# Adafruit_Metro_M4_Express.net
KiCad netlist of a schematic drawn in EAGLE
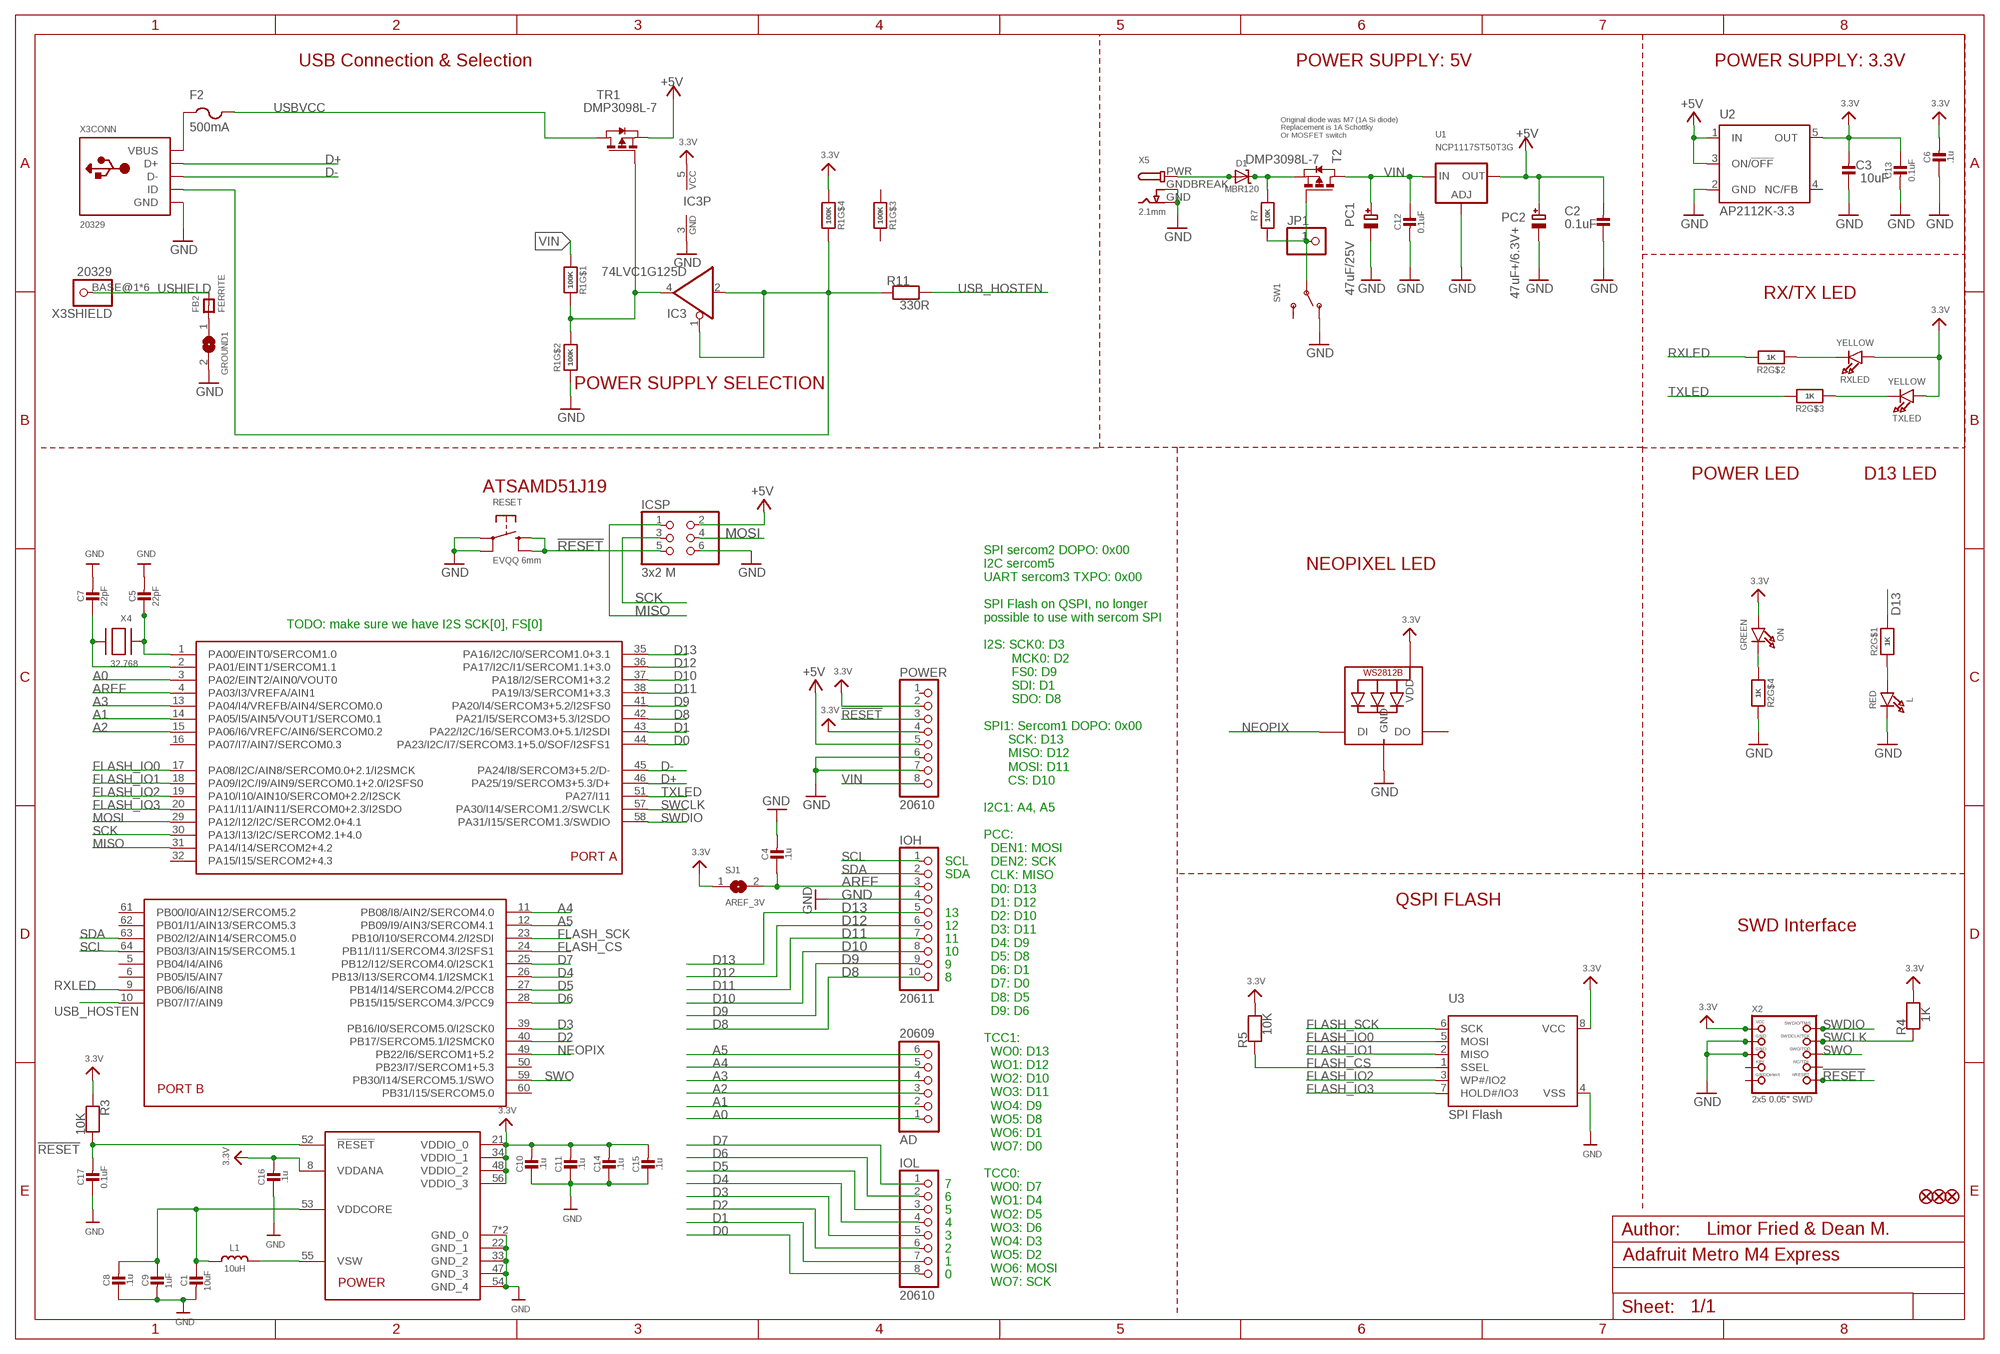
[diagram p0: schematic, sheet 1]

(export (version "E")
  (design (tool "Eeschema 10.0.6"))
  (components
    (comp (ref "AD")
      (value "20609")
      (footprint "eagle-import:1X06_OVALWAVE")
      (libsource (lib "eagle-import") (part "HEADER-1X6OVALWAVE"))
    )
    (comp (ref "C1")
      (value "10uF")
      (footprint "eagle-import:0805-NO")
      (libsource (lib "eagle-import") (part "CAP_CERAMIC0805-NOOUTLINE"))
    )
    (comp (ref "C2")
      (value "0.1uF")
      (footprint "eagle-import:0805-NO")
      (libsource (lib "eagle-import") (part "CAP_CERAMIC0805-NOOUTLINE"))
    )
    (comp (ref "C3")
      (value "10uF")
      (footprint "eagle-import:0805-NO")
      (libsource (lib "eagle-import") (part "CAP_CERAMIC0805-NOOUTLINE"))
    )
    (comp (ref "C4")
      (value ".1u")
      (footprint "eagle-import:0603-NO")
      (libsource (lib "eagle-import") (part "CAP_CERAMIC0603_NO"))
    )
    (comp (ref "C5")
      (value "22pF")
      (footprint "eagle-import:0603-NO")
      (libsource (lib "eagle-import") (part "CAP_CERAMIC0603_NO"))
    )
    (comp (ref "C6")
      (value ".1u")
      (footprint "eagle-import:0603-NO")
      (libsource (lib "eagle-import") (part "CAP_CERAMIC0603_NO"))
    )
    (comp (ref "C7")
      (value "22pF")
      (footprint "eagle-import:0603-NO")
      (libsource (lib "eagle-import") (part "CAP_CERAMIC0603_NO"))
    )
    (comp (ref "C8")
      (value ".1u")
      (footprint "eagle-import:0603-NO")
      (libsource (lib "eagle-import") (part "CAP_CERAMIC0603_NO"))
    )
    (comp (ref "C9")
      (value "1uF")
      (footprint "eagle-import:0603-NO")
      (libsource (lib "eagle-import") (part "CAP_CERAMIC0603_NO"))
    )
    (comp (ref "C10")
      (value ".1u")
      (footprint "eagle-import:0603-NO")
      (libsource (lib "eagle-import") (part "CAP_CERAMIC0603_NO"))
    )
    (comp (ref "C11")
      (value ".1u")
      (footprint "eagle-import:0603-NO")
      (libsource (lib "eagle-import") (part "CAP_CERAMIC0603_NO"))
    )
    (comp (ref "C12")
      (value "0.1uF")
      (footprint "eagle-import:0603-NO")
      (libsource (lib "eagle-import") (part "CAP_CERAMIC0603_NO"))
    )
    (comp (ref "C13")
      (value "0.1uF")
      (footprint "eagle-import:0603-NO")
      (libsource (lib "eagle-import") (part "CAP_CERAMIC0603_NO"))
    )
    (comp (ref "C14")
      (value ".1u")
      (footprint "eagle-import:0603-NO")
      (libsource (lib "eagle-import") (part "CAP_CERAMIC0603_NO"))
    )
    (comp (ref "C15")
      (value ".1u")
      (footprint "eagle-import:0603-NO")
      (libsource (lib "eagle-import") (part "CAP_CERAMIC0603_NO"))
    )
    (comp (ref "C16")
      (value ".1u")
      (footprint "eagle-import:0603-NO")
      (libsource (lib "eagle-import") (part "CAP_CERAMIC0603_NO"))
    )
    (comp (ref "C17")
      (value "0.1uF")
      (footprint "eagle-import:0603-NO")
      (libsource (lib "eagle-import") (part "CAP_CERAMIC0603_NO"))
    )
    (comp (ref "D1")
      (value "MBR120")
      (footprint "eagle-import:SOD-123")
      (libsource (lib "eagle-import") (part "DIODE-SCHOTTKYSOD-123"))
    )
    (comp (ref "F2")
      (value "500mA")
      (footprint "eagle-import:R1206")
      (libsource (lib "eagle-import") (part "PTCFUSE-1206"))
    )
    (comp (ref "FB2")
      (value "FERRITE")
      (footprint "eagle-import:0805-NO")
      (libsource (lib "eagle-import") (part "FERRITE-0805NO"))
    )
    (comp (ref "FD1")
      (value "FIDUCIAL_1MM")
      (footprint "eagle-import:FIDUCIAL_1MM")
      (libsource (lib "eagle-import") (part "FIDUCIAL_1MM"))
    )
    (comp (ref "FD2")
      (value "FIDUCIAL_1MM")
      (footprint "eagle-import:FIDUCIAL_1MM")
      (libsource (lib "eagle-import") (part "FIDUCIAL_1MM"))
    )
    (comp (ref "FD3")
      (value "FIDUCIAL_1MM")
      (footprint "eagle-import:FIDUCIAL_1MM")
      (libsource (lib "eagle-import") (part "FIDUCIAL_1MM"))
    )
    (comp (ref "GROUND1")
      (value "SOLDERJUMPERCLOSED")
      (footprint "eagle-import:SOLDERJUMPER_CLOSEDWIRE")
      (libsource (lib "eagle-import") (part "SOLDERJUMPERCLOSED"))
    )
    (comp (ref "IC3")
      (value "74LVC1G125D")
      (footprint "eagle-import:SOT23-5")
      (libsource (lib "eagle-import") (part "741G125DBVAHC"))
    )
    (comp (ref "ICSP")
      (value "3x2 M")
      (footprint "eagle-import:2X03_ROUND_70MIL")
      (libsource (lib "eagle-import") (part "HEADER-2X3"))
    )
    (comp (ref "IOH")
      (value "20611")
      (footprint "eagle-import:1X10_OVALWAVE")
      (libsource (lib "eagle-import") (part "HEADER-1X10OVALWAVE"))
    )
    (comp (ref "IOL")
      (value "20610")
      (footprint "eagle-import:1X08_OVALWAVE")
      (libsource (lib "eagle-import") (part "HEADER-1X8OVALWAVE"))
    )
    (comp (ref "JP1")
      (value "HEADER-1X1ROUND")
      (footprint "eagle-import:1X01_ROUND")
      (libsource (lib "eagle-import") (part "HEADER-1X1ROUND"))
    )
    (comp (ref "L")
      (value "RED")
      (footprint "eagle-import:CHIPLED_0805_NOOUTLINE")
      (libsource (lib "eagle-import") (part "LED0805_NOOUTLINE"))
    )
    (comp (ref "L1")
      (value "10uH")
      (footprint "eagle-import:INDUCTOR_1007")
      (libsource (lib "eagle-import") (part "INDUCTOR"))
    )
    (comp (ref "LED1")
      (value "WS2812B3535")
      (footprint "eagle-import:LED3535")
      (libsource (lib "eagle-import") (part "WS2812B3535"))
    )
    (comp (ref "ON")
      (value "GREEN")
      (footprint "eagle-import:CHIPLED_0805_NOOUTLINE")
      (libsource (lib "eagle-import") (part "LED0805_NOOUTLINE"))
    )
    (comp (ref "PC1")
      (value "47uF/25V")
      (footprint "eagle-import:PANASONIC_D")
      (libsource (lib "eagle-import") (part "CAP_ELECTROLYTICPANASONIC_D"))
    )
    (comp (ref "PC2")
      (value "47uF+/6.3V+")
      (footprint "eagle-import:PANASONIC_D")
      (libsource (lib "eagle-import") (part "CAP_ELECTROLYTICPANASONIC_D"))
    )
    (comp (ref "POWER")
      (value "20610")
      (footprint "eagle-import:1X08_OVALWAVE")
      (libsource (lib "eagle-import") (part "HEADER-1X8OVALWAVE"))
    )
    (comp (ref "R1")
      (value "100K")
      (footprint "eagle-import:RESPACK_4X0603")
      (libsource (lib "eagle-import") (part "RESISTOR_4PACK"))
    )
    (comp (ref "R2")
      (value "1K")
      (footprint "eagle-import:RESPACK_4X0603")
      (libsource (lib "eagle-import") (part "RESISTOR_4PACK"))
    )
    (comp (ref "R3")
      (value "10K")
      (footprint "eagle-import:0603-NO")
      (libsource (lib "eagle-import") (part "RESISTOR_0603_NOOUT"))
    )
    (comp (ref "R4")
      (value "1K")
      (footprint "eagle-import:0603-NO")
      (libsource (lib "eagle-import") (part "RESISTOR_0603_NOOUT"))
    )
    (comp (ref "R5")
      (value "10K")
      (footprint "eagle-import:0603-NO")
      (libsource (lib "eagle-import") (part "RESISTOR_0603_NOOUT"))
    )
    (comp (ref "R7")
      (value "10K")
      (footprint "eagle-import:0603-NO")
      (libsource (lib "eagle-import") (part "RESISTOR_0603_NOOUT"))
    )
    (comp (ref "R11")
      (value "330R")
      (footprint "eagle-import:0603-NO")
      (libsource (lib "eagle-import") (part "RESISTOR_0603_NOOUT"))
    )
    (comp (ref "RESET")
      (value "EVQQ 6mm")
      (footprint "eagle-import:EVQ-Q2")
      (libsource (lib "eagle-import") (part "SWITCH_TACT_SMT"))
    )
    (comp (ref "RXLED")
      (value "YELLOW")
      (footprint "eagle-import:CHIPLED_0805_NOOUTLINE")
      (libsource (lib "eagle-import") (part "LED0805_NOOUTLINE"))
    )
    (comp (ref "SJ1")
      (value "AREF_3V")
      (footprint "eagle-import:SOLDERJUMPER_CLOSEDWIRE")
      (libsource (lib "eagle-import") (part "SOLDERJUMPERCLOSED"))
    )
    (comp (ref "SW1")
      (value "SWITCH_SPDT")
      (footprint "eagle-import:SPDT_SMT_SSSS811101")
      (libsource (lib "eagle-import") (part "SWITCH_SPDT"))
    )
    (comp (ref "T2")
      (value "DMP3098L-7")
      (footprint "eagle-import:SOT-23")
      (libsource (lib "eagle-import") (part "PMOSSOT23"))
    )
    (comp (ref "TR1")
      (value "DMP3098L-7")
      (footprint "eagle-import:SOT-23")
      (fields (field (name "PART_NUMBER") "PMV48XP"))
      (libsource (lib "eagle-import") (part "0297_PMV48XP"))
    )
    (comp (ref "TXLED")
      (value "YELLOW")
      (footprint "eagle-import:CHIPLED_0805_NOOUTLINE")
      (libsource (lib "eagle-import") (part "LED0805_NOOUTLINE"))
    )
    (comp (ref "U$1")
      (value "ATSAMD51J")
      (footprint "eagle-import:PQFN64-1")
      (libsource (lib "eagle-import") (part "ATSAMD51J"))
    )
    (comp (ref "U1")
      (value "NCP1117ST50T3G")
      (footprint "eagle-import:SOT223-R")
      (libsource (lib "eagle-import") (part "LM1117SOT223-REFLOW"))
    )
    (comp (ref "U2")
      (value "AP2112K-3.3")
      (footprint "eagle-import:SOT23-DBV")
      (libsource (lib "eagle-import") (part "LP2985-XXDBVR33"))
    )
    (comp (ref "U3")
      (value "SPI Flash")
      (footprint "eagle-import:SOIC8_208MIL")
      (libsource (lib "eagle-import") (part "SPIFLASH_SOIC8208MIL"))
    )
    (comp (ref "X2")
      (value "2x5 0.05\" SWD")
      (footprint "eagle-import:2X05_1.27MM_BOX_POSTS")
      (libsource (lib "eagle-import") (part "JTAG-CORTEXBOXPOSTS"))
    )
    (comp (ref "X3")
      (value "20329")
      (footprint "eagle-import:4UCONN_20329_V2")
      (libsource (lib "eagle-import") (part "USB_W_SHIELD_V2"))
    )
    (comp (ref "X4")
      (value "32.768")
      (footprint "eagle-import:XTAL3215")
      (libsource (lib "eagle-import") (part "XTAL-3.2X1.5"))
    )
    (comp (ref "X5")
      (value "2.1mm")
      (footprint "eagle-import:DCJACK_2MM_PTH")
      (libsource (lib "eagle-import") (part "DCBARRELPTH"))
    )
  )
  (nets
    (net (code "1") (name "+5V") (class "Default")
      (node (ref "C2") (pin "2") (pinfunction "2_2") (pintype "passive"))
      (node (ref "ICSP") (pin "2") (pinfunction "2_2") (pintype "passive"))
      (node (ref "PC2") (pin "+") (pinfunction "+_+") (pintype "passive"))
      (node (ref "POWER") (pin "5") (pinfunction "5_5") (pintype "passive"))
      (node (ref "TR1") (pin "2") (pinfunction "S_2") (pintype "passive"))
      (node (ref "U1") (pin "2") (pinfunction "OUT_2") (pintype "passive"))
      (node (ref "U1") (pin "4") (pinfunction "OUT_4") (pintype "passive"))
      (node (ref "U2") (pin "1") (pinfunction "IN_1") (pintype "input"))
      (node (ref "U2") (pin "3") (pinfunction "ON/~{OFF}_3") (pintype "input"))
    )
    (net (code "2") (name "/A0") (class "Default")
      (node (ref "AD") (pin "1") (pinfunction "1_1") (pintype "passive"))
      (node (ref "U$1") (pin "3") (pinfunction "PA02/EINT2/AIN0/VOUT0_3") (pintype "bidirectional"))
    )
    (net (code "3") (name "/A1") (class "Default")
      (node (ref "AD") (pin "2") (pinfunction "2_2") (pintype "passive"))
      (node (ref "U$1") (pin "14") (pinfunction "PA05/I5/AIN5/VOUT1/SERCOM0.1_14") (pintype "bidirectional"))
    )
    (net (code "4") (name "/A2") (class "Default")
      (node (ref "AD") (pin "3") (pinfunction "3_3") (pintype "passive"))
      (node (ref "U$1") (pin "15") (pinfunction "PA06/I6/VREFC/AIN6/SERCOM0.2_15") (pintype "bidirectional"))
    )
    (net (code "5") (name "/A3") (class "Default")
      (node (ref "AD") (pin "4") (pinfunction "4_4") (pintype "passive"))
      (node (ref "U$1") (pin "13") (pinfunction "PA04/I4/VREFB/AIN4/SERCOM0.0_13") (pintype "bidirectional"))
    )
    (net (code "6") (name "/A4") (class "Default")
      (node (ref "AD") (pin "5") (pinfunction "5_5") (pintype "passive"))
      (node (ref "U$1") (pin "11") (pinfunction "PB08/I8/AIN2/SERCOM4.0_11") (pintype "bidirectional"))
    )
    (net (code "7") (name "/A5") (class "Default")
      (node (ref "AD") (pin "6") (pinfunction "6_6") (pintype "passive"))
      (node (ref "U$1") (pin "12") (pinfunction "PB09/I9/AIN3/SERCOM4.1_12") (pintype "bidirectional"))
    )
    (net (code "8") (name "/AREF") (class "Default")
      (node (ref "C4") (pin "1") (pinfunction "1_1") (pintype "passive"))
      (node (ref "IOH") (pin "3") (pinfunction "3_3") (pintype "passive"))
      (node (ref "SJ1") (pin "2") (pinfunction "2_2") (pintype "passive"))
      (node (ref "U$1") (pin "4") (pinfunction "PA03/I3/VREFA/AIN1_4") (pintype "bidirectional"))
    )
    (net (code "9") (name "/D+") (class "Default")
      (node (ref "U$1") (pin "46") (pinfunction "PA25/19/SERCOM3+5.3/D+_46") (pintype "bidirectional"))
      (node (ref "X3") (pin "D+") (pinfunction "D+_D+") (pintype "bidirectional"))
    )
    (net (code "10") (name "/D-") (class "Default")
      (node (ref "U$1") (pin "45") (pinfunction "PA24/I8/SERCOM3+5.2/D-_45") (pintype "bidirectional"))
      (node (ref "X3") (pin "D-") (pinfunction "D-_D-") (pintype "bidirectional"))
    )
    (net (code "11") (name "/D0") (class "Default")
      (node (ref "IOL") (pin "8") (pinfunction "8_8") (pintype "passive"))
      (node (ref "U$1") (pin "44") (pinfunction "PA23/I2C/I7/SERCOM3.1+5.0/SOF/I2SFS1_44") (pintype "bidirectional"))
    )
    (net (code "12") (name "/D1") (class "Default")
      (node (ref "IOL") (pin "7") (pinfunction "7_7") (pintype "passive"))
      (node (ref "U$1") (pin "43") (pinfunction "PA22/I2C/16/SERCOM3.0+5.1/I2SDI_43") (pintype "bidirectional"))
    )
    (net (code "13") (name "/D2") (class "Default")
      (node (ref "IOL") (pin "6") (pinfunction "6_6") (pintype "passive"))
      (node (ref "U$1") (pin "40") (pinfunction "PB17/SERCOM5.1/I2SMCK0_40") (pintype "bidirectional"))
    )
    (net (code "14") (name "/D3") (class "Default")
      (node (ref "IOL") (pin "5") (pinfunction "5_5") (pintype "passive"))
      (node (ref "U$1") (pin "39") (pinfunction "PB16/I0/SERCOM5.0/I2SCK0_39") (pintype "bidirectional"))
    )
    (net (code "15") (name "/D4") (class "Default")
      (node (ref "IOL") (pin "4") (pinfunction "4_4") (pintype "passive"))
      (node (ref "U$1") (pin "26") (pinfunction "PB13/I13/SERCOM4.1/I2SMCK1_26") (pintype "bidirectional"))
    )
    (net (code "16") (name "/D5") (class "Default")
      (node (ref "IOL") (pin "3") (pinfunction "3_3") (pintype "passive"))
      (node (ref "U$1") (pin "27") (pinfunction "PB14/I14/SERCOM4.2/PCC8_27") (pintype "bidirectional"))
    )
    (net (code "17") (name "/D6") (class "Default")
      (node (ref "IOL") (pin "2") (pinfunction "2_2") (pintype "passive"))
      (node (ref "U$1") (pin "28") (pinfunction "PB15/I15/SERCOM4.3/PCC9_28") (pintype "bidirectional"))
    )
    (net (code "18") (name "/D7") (class "Default")
      (node (ref "IOL") (pin "1") (pinfunction "1_1") (pintype "passive"))
      (node (ref "U$1") (pin "25") (pinfunction "PB12/I12/SERCOM4.0/I2SCK1_25") (pintype "bidirectional"))
    )
    (net (code "19") (name "/D8") (class "Default")
      (node (ref "IOH") (pin "10") (pinfunction "10_10") (pintype "passive"))
      (node (ref "U$1") (pin "42") (pinfunction "PA21/I5/SERCOM3+5.3/I2SDO_42") (pintype "bidirectional"))
    )
    (net (code "20") (name "/D9") (class "Default")
      (node (ref "IOH") (pin "9") (pinfunction "9_9") (pintype "passive"))
      (node (ref "U$1") (pin "41") (pinfunction "PA20/I4/SERCOM3+5.2/I2SFS0_41") (pintype "bidirectional"))
    )
    (net (code "21") (name "/D10") (class "Default")
      (node (ref "IOH") (pin "8") (pinfunction "8_8") (pintype "passive"))
      (node (ref "U$1") (pin "37") (pinfunction "PA18/I2/SERCOM1+3.2_37") (pintype "bidirectional"))
    )
    (net (code "22") (name "/D11") (class "Default")
      (node (ref "IOH") (pin "7") (pinfunction "7_7") (pintype "passive"))
      (node (ref "U$1") (pin "38") (pinfunction "PA19/I3/SERCOM1+3.3_38") (pintype "bidirectional"))
    )
    (net (code "23") (name "/D12") (class "Default")
      (node (ref "IOH") (pin "6") (pinfunction "6_6") (pintype "passive"))
      (node (ref "U$1") (pin "36") (pinfunction "PA17/I2C/I1/SERCOM1.1+3.0_36") (pintype "bidirectional"))
    )
    (net (code "24") (name "/D13") (class "Default")
      (node (ref "IOH") (pin "5") (pinfunction "5_5") (pintype "passive"))
      (node (ref "R2") (pin "8") (pinfunction "2_8") (pintype "passive"))
      (node (ref "U$1") (pin "35") (pinfunction "PA16/I2C/I0/SERCOM1.0+3.1_35") (pintype "bidirectional"))
    )
    (net (code "25") (name "/FLASH_CS") (class "Default")
      (node (ref "R5") (pin "1") (pinfunction "1_1") (pintype "passive"))
      (node (ref "U$1") (pin "24") (pinfunction "PB11/I11/SERCOM4.3/I2SFS1_24") (pintype "bidirectional"))
      (node (ref "U3") (pin "1") (pinfunction "SSEL_1") (pintype "bidirectional"))
    )
    (net (code "26") (name "/FLASH_IO0") (class "Default")
      (node (ref "U$1") (pin "17") (pinfunction "PA08/I2C/AIN8/SERCOM0.0+2.1/I2SMCK_17") (pintype "bidirectional"))
      (node (ref "U3") (pin "5") (pinfunction "MOSI_5") (pintype "bidirectional"))
    )
    (net (code "27") (name "/FLASH_IO1") (class "Default")
      (node (ref "U$1") (pin "18") (pinfunction "PA09/I2C/I9/AIN9/SERCOM0.1+2.0/I2SFS0_18") (pintype "bidirectional"))
      (node (ref "U3") (pin "2") (pinfunction "MISO_2") (pintype "bidirectional"))
    )
    (net (code "28") (name "/FLASH_IO2") (class "Default")
      (node (ref "U$1") (pin "19") (pinfunction "PA10/I10/AIN10/SERCOM0+2.2/I2SCK_19") (pintype "bidirectional"))
      (node (ref "U3") (pin "3") (pinfunction "WP#/IO2_3") (pintype "bidirectional"))
    )
    (net (code "29") (name "/FLASH_IO3") (class "Default")
      (node (ref "U$1") (pin "20") (pinfunction "PA11/I11/AIN11/SERCOM0+2.3/I2SDO_20") (pintype "bidirectional"))
      (node (ref "U3") (pin "7") (pinfunction "HOLD#/IO3_7") (pintype "bidirectional"))
    )
    (net (code "30") (name "/FLASH_SCK") (class "Default")
      (node (ref "U$1") (pin "23") (pinfunction "PB10/I10/SERCOM4.2/I2SDI_23") (pintype "bidirectional"))
      (node (ref "U3") (pin "6") (pinfunction "SCK_6") (pintype "bidirectional"))
    )
    (net (code "31") (name "/MISO") (class "Default")
      (node (ref "ICSP") (pin "1") (pinfunction "1_1") (pintype "passive"))
      (node (ref "U$1") (pin "31") (pinfunction "PA14/I14/SERCOM2+4.2_31") (pintype "bidirectional"))
    )
    (net (code "32") (name "/MOSI") (class "Default")
      (node (ref "ICSP") (pin "4") (pinfunction "4_4") (pintype "passive"))
      (node (ref "U$1") (pin "29") (pinfunction "PA12/I12/I2C/SERCOM2.0+4.1_29") (pintype "bidirectional"))
    )
    (net (code "33") (name "/NEOPIX") (class "Default")
      (node (ref "LED1") (pin "1") (pinfunction "DI_1") (pintype "input"))
      (node (ref "U$1") (pin "49") (pinfunction "PB22/I6/SERCOM1+5.2_49") (pintype "bidirectional"))
    )
    (net (code "34") (name "/RXLED") (class "Default")
      (node (ref "R2") (pin "7") (pinfunction "2_7") (pintype "passive"))
      (node (ref "U$1") (pin "9") (pinfunction "PB06/I6/AIN8_9") (pintype "bidirectional"))
    )
    (net (code "35") (name "/SCK") (class "Default")
      (node (ref "ICSP") (pin "3") (pinfunction "3_3") (pintype "passive"))
      (node (ref "U$1") (pin "30") (pinfunction "PA13/I13/I2C/SERCOM2.1+4.0_30") (pintype "bidirectional"))
    )
    (net (code "36") (name "/SCL") (class "Default")
      (node (ref "IOH") (pin "1") (pinfunction "1_1") (pintype "passive"))
      (node (ref "U$1") (pin "64") (pinfunction "PB03/I3/AIN15/SERCOM5.1_64") (pintype "bidirectional"))
    )
    (net (code "37") (name "/SDA") (class "Default")
      (node (ref "IOH") (pin "2") (pinfunction "2_2") (pintype "passive"))
      (node (ref "U$1") (pin "63") (pinfunction "PB02/I2/AIN14/SERCOM5.0_63") (pintype "bidirectional"))
    )
    (net (code "38") (name "/SWCLK") (class "Default")
      (node (ref "R4") (pin "1") (pinfunction "1_1") (pintype "passive"))
      (node (ref "U$1") (pin "57") (pinfunction "PA30/I14/SERCOM1.2/SWCLK_57") (pintype "bidirectional"))
      (node (ref "X2") (pin "4") (pinfunction "SWDCLK_4") (pintype "bidirectional"))
    )
    (net (code "39") (name "/SWDIO") (class "Default")
      (node (ref "U$1") (pin "58") (pinfunction "PA31/I15/SERCOM1.3/SWDIO_58") (pintype "bidirectional"))
      (node (ref "X2") (pin "2") (pinfunction "SWDIO_2") (pintype "bidirectional"))
    )
    (net (code "40") (name "/SWO") (class "Default")
      (node (ref "U$1") (pin "59") (pinfunction "PB30/I14/SERCOM5.1/SWO_59") (pintype "bidirectional"))
      (node (ref "X2") (pin "6") (pinfunction "SWO_6") (pintype "bidirectional"))
    )
    (net (code "41") (name "/TXLED") (class "Default")
      (node (ref "R2") (pin "6") (pinfunction "2_6") (pintype "passive"))
      (node (ref "U$1") (pin "51") (pinfunction "PA27/I11_51") (pintype "bidirectional"))
    )
    (net (code "42") (name "/USBVCC") (class "Default")
      (node (ref "F2") (pin "2") (pinfunction "2_2") (pintype "passive"))
      (node (ref "TR1") (pin "1") (pinfunction "D_1") (pintype "passive"))
    )
    (net (code "43") (name "/USB_HOSTEN") (class "Default")
      (node (ref "R11") (pin "2") (pinfunction "2_2") (pintype "passive"))
      (node (ref "U$1") (pin "10") (pinfunction "PB07/I7/AIN9_10") (pintype "bidirectional"))
    )
    (net (code "44") (name "/USHIELD") (class "Default")
      (node (ref "FB2") (pin "2") (pinfunction "P$2_2") (pintype "passive"))
      (node (ref "X3") (pin "BASE@1") (pinfunction "1_BASE@1") (pintype "passive"))
      (node (ref "X3") (pin "BASE@2") (pinfunction "1_BASE@2") (pintype "passive"))
      (node (ref "X3") (pin "SPRT@1") (pinfunction "1_SPRT@1") (pintype "passive"))
      (node (ref "X3") (pin "SPRT@2") (pinfunction "1_SPRT@2") (pintype "passive"))
      (node (ref "X3") (pin "SPRT@3") (pinfunction "1_SPRT@3") (pintype "passive"))
      (node (ref "X3") (pin "SPRT@4") (pinfunction "1_SPRT@4") (pintype "passive"))
    )
    (net (code "45") (name "/~{RESET}") (class "Default")
      (node (ref "C17") (pin "2") (pinfunction "2_2") (pintype "passive"))
      (node (ref "ICSP") (pin "5") (pinfunction "5_5") (pintype "passive"))
      (node (ref "POWER") (pin "3") (pinfunction "3_3") (pintype "passive"))
      (node (ref "R3") (pin "2") (pinfunction "2_2") (pintype "passive"))
      (node (ref "RESET") (pin "B") (pinfunction "S_B") (pintype "passive"))
      (node (ref "RESET") (pin "B'") (pinfunction "S1_B'") (pintype "passive"))
      (node (ref "U$1") (pin "52") (pinfunction "~{RESET}_52") (pintype "bidirectional"))
      (node (ref "X2") (pin "10") (pinfunction "NRESET_10") (pintype "bidirectional"))
    )
    (net (code "46") (name "3.3V") (class "Default")
      (node (ref "C10") (pin "2") (pinfunction "2_2") (pintype "passive"))
      (node (ref "C11") (pin "2") (pinfunction "2_2") (pintype "passive"))
      (node (ref "C13") (pin "1") (pinfunction "1_1") (pintype "passive"))
      (node (ref "C14") (pin "2") (pinfunction "2_2") (pintype "passive"))
      (node (ref "C15") (pin "2") (pinfunction "2_2") (pintype "passive"))
      (node (ref "C16") (pin "2") (pinfunction "2_2") (pintype "passive"))
      (node (ref "C3") (pin "2") (pinfunction "2_2") (pintype "passive"))
      (node (ref "C6") (pin "2") (pinfunction "2_2") (pintype "passive"))
      (node (ref "IC3") (pin "5") (pinfunction "VCC_5") (pintype "power_in"))
      (node (ref "LED1") (pin "2") (pinfunction "VDD_2") (pintype "power_in"))
      (node (ref "ON") (pin "A") (pinfunction "A_A") (pintype "passive"))
      (node (ref "POWER") (pin "2") (pinfunction "2_2") (pintype "passive"))
      (node (ref "POWER") (pin "4") (pinfunction "4_4") (pintype "passive"))
      (node (ref "R1") (pin "4") (pinfunction "1_4") (pintype "passive"))
      (node (ref "R3") (pin "1") (pinfunction "1_1") (pintype "passive"))
      (node (ref "R4") (pin "2") (pinfunction "2_2") (pintype "passive"))
      (node (ref "R5") (pin "2") (pinfunction "2_2") (pintype "passive"))
      (node (ref "RXLED") (pin "A") (pinfunction "A_A") (pintype "passive"))
      (node (ref "SJ1") (pin "1") (pinfunction "1_1") (pintype "passive"))
      (node (ref "TXLED") (pin "A") (pinfunction "A_A") (pintype "passive"))
      (node (ref "U$1") (pin "21") (pinfunction "VDDIO_0_21") (pintype "bidirectional"))
      (node (ref "U$1") (pin "34") (pinfunction "VDDIO_1_34") (pintype "bidirectional"))
      (node (ref "U$1") (pin "48") (pinfunction "VDDIO_2_48") (pintype "bidirectional"))
      (node (ref "U$1") (pin "56") (pinfunction "VDDIO_3_56") (pintype "bidirectional"))
      (node (ref "U$1") (pin "8") (pinfunction "VDDANA_8") (pintype "bidirectional"))
      (node (ref "U2") (pin "5") (pinfunction "OUT_5") (pintype "passive"))
      (node (ref "U3") (pin "8") (pinfunction "VCC_8") (pintype "bidirectional"))
      (node (ref "X2") (pin "1") (pinfunction "VCC_1") (pintype "power_in"))
    )
    (net (code "47") (name "GND") (class "Default")
      (node (ref "C1") (pin "2") (pinfunction "2_2") (pintype "passive"))
      (node (ref "C10") (pin "1") (pinfunction "1_1") (pintype "passive"))
      (node (ref "C11") (pin "1") (pinfunction "1_1") (pintype "passive"))
      (node (ref "C12") (pin "2") (pinfunction "2_2") (pintype "passive"))
      (node (ref "C13") (pin "2") (pinfunction "2_2") (pintype "passive"))
      (node (ref "C14") (pin "1") (pinfunction "1_1") (pintype "passive"))
      (node (ref "C15") (pin "1") (pinfunction "1_1") (pintype "passive"))
      (node (ref "C16") (pin "1") (pinfunction "1_1") (pintype "passive"))
      (node (ref "C17") (pin "1") (pinfunction "1_1") (pintype "passive"))
      (node (ref "C2") (pin "1") (pinfunction "1_1") (pintype "passive"))
      (node (ref "C3") (pin "1") (pinfunction "1_1") (pintype "passive"))
      (node (ref "C4") (pin "2") (pinfunction "2_2") (pintype "passive"))
      (node (ref "C5") (pin "2") (pinfunction "2_2") (pintype "passive"))
      (node (ref "C6") (pin "1") (pinfunction "1_1") (pintype "passive"))
      (node (ref "C7") (pin "2") (pinfunction "2_2") (pintype "passive"))
      (node (ref "C8") (pin "1") (pinfunction "1_1") (pintype "passive"))
      (node (ref "C9") (pin "2") (pinfunction "2_2") (pintype "passive"))
      (node (ref "GROUND1") (pin "2") (pinfunction "2_2") (pintype "passive"))
      (node (ref "IC3") (pin "3") (pinfunction "GND_3") (pintype "power_in"))
      (node (ref "ICSP") (pin "6") (pinfunction "6_6") (pintype "passive"))
      (node (ref "IOH") (pin "4") (pinfunction "4_4") (pintype "passive"))
      (node (ref "L") (pin "C") (pinfunction "C_C") (pintype "passive"))
      (node (ref "LED1") (pin "4") (pinfunction "GND_4") (pintype "power_in"))
      (node (ref "PC1") (pin "-") (pinfunction "-_-") (pintype "passive"))
      (node (ref "PC2") (pin "-") (pinfunction "-_-") (pintype "passive"))
      (node (ref "POWER") (pin "6") (pinfunction "6_6") (pintype "passive"))
      (node (ref "POWER") (pin "7") (pinfunction "7_7") (pintype "passive"))
      (node (ref "R1") (pin "2") (pinfunction "1_2") (pintype "passive"))
      (node (ref "R2") (pin "5") (pinfunction "2_5") (pintype "passive"))
      (node (ref "RESET") (pin "A") (pinfunction "P_A") (pintype "passive"))
      (node (ref "RESET") (pin "A'") (pinfunction "P1_A'") (pintype "passive"))
      (node (ref "SW1") (pin "A") (pinfunction "O_A") (pintype "passive"))
      (node (ref "U$1") (pin "22") (pinfunction "GND_1_22") (pintype "bidirectional"))
      (node (ref "U$1") (pin "33") (pinfunction "GND_2_33") (pintype "bidirectional"))
      (node (ref "U$1") (pin "47") (pinfunction "GND_3_47") (pintype "bidirectional"))
      (node (ref "U$1") (pin "54") (pinfunction "GND_4_54") (pintype "bidirectional"))
      (node (ref "U$1") (pin "7") (pinfunction "GND_0_7") (pintype "bidirectional"))
      (node (ref "U$1") (pin "EXP") (pinfunction "GND_0_EXP") (pintype "bidirectional"))
      (node (ref "U1") (pin "1") (pinfunction "ADJ_1") (pintype "input"))
      (node (ref "U2") (pin "2") (pinfunction "GND_2") (pintype "power_in"))
      (node (ref "U3") (pin "4") (pinfunction "VSS_4") (pintype "bidirectional"))
      (node (ref "X2") (pin "3") (pinfunction "GND_3") (pintype "power_in"))
      (node (ref "X2") (pin "5") (pinfunction "GND_5") (pintype "power_in"))
      (node (ref "X3") (pin "GND") (pinfunction "GND_GND") (pintype "power_in"))
      (node (ref "X5") (pin "GND") (pinfunction "GND_GND") (pintype "power_in"))
      (node (ref "X5") (pin "GNDBREAK") (pinfunction "GNDBREAK_GNDBREAK") (pintype "power_in"))
    )
    (net (code "48") (name "Net-(D1-PadA)") (class "Default")
      (node (ref "D1") (pin "A") (pinfunction "A_A") (pintype "passive"))
      (node (ref "X5") (pin "PWR") (pinfunction "PWR_PWR") (pintype "power_in"))
    )
    (net (code "49") (name "Net-(F2-Pad1)") (class "Default")
      (node (ref "F2") (pin "1") (pinfunction "1_1") (pintype "passive"))
      (node (ref "X3") (pin "VBUS") (pinfunction "VBUS_VBUS") (pintype "power_in"))
    )
    (net (code "50") (name "Net-(FB2-P$1)") (class "Default")
      (node (ref "FB2") (pin "1") (pinfunction "P$1_1") (pintype "passive"))
      (node (ref "GROUND1") (pin "1") (pinfunction "1_1") (pintype "passive"))
    )
    (net (code "51") (name "Net-(IC3A-I)") (class "Default")
      (node (ref "IC3") (pin "1") (pinfunction "OE_1") (pintype "input"))
      (node (ref "IC3") (pin "2") (pinfunction "I_2") (pintype "input"))
      (node (ref "R1") (pin "5") (pinfunction "2_5") (pintype "passive"))
      (node (ref "R11") (pin "1") (pinfunction "1_1") (pintype "passive"))
      (node (ref "X3") (pin "ID") (pinfunction "ID_ID") (pintype "bidirectional"))
    )
    (net (code "52") (name "Net-(IC3A-O)") (class "Default")
      (node (ref "IC3") (pin "4") (pinfunction "O_4") (pintype "tri_state"))
      (node (ref "R1") (pin "7") (pinfunction "2_7") (pintype "passive"))
      (node (ref "R1") (pin "8") (pinfunction "2_8") (pintype "passive"))
      (node (ref "TR1") (pin "3") (pinfunction "G_3") (pintype "passive"))
    )
    (net (code "53") (name "Net-(L-PadA)") (class "Default")
      (node (ref "L") (pin "A") (pinfunction "A_A") (pintype "passive"))
      (node (ref "R2") (pin "1") (pinfunction "1_1") (pintype "passive"))
    )
    (net (code "54") (name "Net-(L1-1)") (class "Default")
      (node (ref "C1") (pin "1") (pinfunction "1_1") (pintype "passive"))
      (node (ref "C8") (pin "2") (pinfunction "2_2") (pintype "passive"))
      (node (ref "C9") (pin "1") (pinfunction "1_1") (pintype "passive"))
      (node (ref "L1") (pin "P$1") (pinfunction "1_P$1") (pintype "passive"))
      (node (ref "U$1") (pin "53") (pinfunction "VDDCORE_53") (pintype "bidirectional"))
    )
    (net (code "55") (name "Net-(L1-2)") (class "Default")
      (node (ref "L1") (pin "P$2") (pinfunction "2_P$2") (pintype "passive"))
      (node (ref "U$1") (pin "55") (pinfunction "VSW_55") (pintype "bidirectional"))
    )
    (net (code "56") (name "Net-(R2B-1)") (class "Default")
      (node (ref "R2") (pin "2") (pinfunction "1_2") (pintype "passive"))
      (node (ref "RXLED") (pin "C") (pinfunction "C_C") (pintype "passive"))
    )
    (net (code "57") (name "Net-(R2C-1)") (class "Default")
      (node (ref "R2") (pin "3") (pinfunction "1_3") (pintype "passive"))
      (node (ref "TXLED") (pin "C") (pinfunction "C_C") (pintype "passive"))
    )
    (net (code "58") (name "Net-(R2D-1)") (class "Default")
      (node (ref "ON") (pin "C") (pinfunction "C_C") (pintype "passive"))
      (node (ref "R2") (pin "4") (pinfunction "1_4") (pintype "passive"))
    )
    (net (code "59") (name "Net-(SW1-P)") (class "Default")
      (node (ref "JP1") (pin "1") (pinfunction "1_1") (pintype "passive"))
      (node (ref "R7") (pin "1") (pinfunction "1_1") (pintype "passive"))
      (node (ref "SW1") (pin "B") (pinfunction "P_B") (pintype "passive"))
      (node (ref "T2") (pin "3") (pinfunction "G_3") (pintype "passive"))
    )
    (net (code "60") (name "Net-(T2-S)") (class "Default")
      (node (ref "D1") (pin "C") (pinfunction "C_C") (pintype "passive"))
      (node (ref "R7") (pin "2") (pinfunction "2_2") (pintype "passive"))
      (node (ref "T2") (pin "2") (pinfunction "S_2") (pintype "passive"))
    )
    (net (code "61") (name "Net-(U$1A-PA00{slash}EINT0{slash}SERCOM1.0)") (class "Default")
      (node (ref "C5") (pin "1") (pinfunction "1_1") (pintype "passive"))
      (node (ref "U$1") (pin "1") (pinfunction "PA00/EINT0/SERCOM1.0_1") (pintype "bidirectional"))
      (node (ref "X4") (pin "P$1") (pinfunction "P$1_P$1") (pintype "bidirectional"))
    )
    (net (code "62") (name "Net-(U$1A-PA01{slash}EINT1{slash}SERCOM1.1)") (class "Default")
      (node (ref "C7") (pin "1") (pinfunction "1_1") (pintype "passive"))
      (node (ref "U$1") (pin "2") (pinfunction "PA01/EINT1/SERCOM1.1_2") (pintype "bidirectional"))
      (node (ref "X4") (pin "P$2") (pinfunction "P$2_P$2") (pintype "bidirectional"))
    )
    (net (code "63") (name "VIN") (class "Default")
      (node (ref "C12") (pin "1") (pinfunction "1_1") (pintype "passive"))
      (node (ref "PC1") (pin "+") (pinfunction "+_+") (pintype "passive"))
      (node (ref "POWER") (pin "8") (pinfunction "8_8") (pintype "passive"))
      (node (ref "R1") (pin "1") (pinfunction "1_1") (pintype "passive"))
      (node (ref "T2") (pin "1") (pinfunction "D_1") (pintype "passive"))
      (node (ref "U1") (pin "3") (pinfunction "IN_3") (pintype "input"))
    )
    (net (code "64") (name "unconnected-(LED1-DO-Pad3)") (class "Default")
      (node (ref "LED1") (pin "3") (pinfunction "DO_3") (pintype "output"))
    )
    (net (code "65") (name "unconnected-(POWER-Pad1)") (class "Default")
      (node (ref "POWER") (pin "1") (pinfunction "1_1") (pintype "passive"))
    )
    (net (code "66") (name "unconnected-(R1C-1-Pad3)") (class "Default")
      (node (ref "R1") (pin "3") (pinfunction "1_3") (pintype "passive"))
    )
    (net (code "67") (name "unconnected-(R1C-2-Pad6)") (class "Default")
      (node (ref "R1") (pin "6") (pinfunction "2_6") (pintype "passive"))
    )
    (net (code "68") (name "unconnected-(SW1-S-PadC)") (class "Default")
      (node (ref "SW1") (pin "C") (pinfunction "S_C") (pintype "passive"))
    )
    (net (code "69") (name "unconnected-(U$1A-PA07{slash}I7{slash}AIN7{slash}SERCOM0.3-Pad16)") (class "Default")
      (node (ref "U$1") (pin "16") (pinfunction "PA07/I7/AIN7/SERCOM0.3_16") (pintype "bidirectional"))
    )
    (net (code "70") (name "unconnected-(U$1A-PA15{slash}I15{slash}SERCOM2+4.3-Pad32)") (class "Default")
      (node (ref "U$1") (pin "32") (pinfunction "PA15/I15/SERCOM2+4.3_32") (pintype "bidirectional"))
    )
    (net (code "71") (name "unconnected-(U$1B-PB00{slash}I0{slash}AIN12{slash}SERCOM5.2-Pad61)") (class "Default")
      (node (ref "U$1") (pin "61") (pinfunction "PB00/I0/AIN12/SERCOM5.2_61") (pintype "bidirectional"))
    )
    (net (code "72") (name "unconnected-(U$1B-PB01{slash}I1{slash}AIN13{slash}SERCOM5.3-Pad62)") (class "Default")
      (node (ref "U$1") (pin "62") (pinfunction "PB01/I1/AIN13/SERCOM5.3_62") (pintype "bidirectional"))
    )
    (net (code "73") (name "unconnected-(U$1B-PB04{slash}I4{slash}AIN6-Pad5)") (class "Default")
      (node (ref "U$1") (pin "5") (pinfunction "PB04/I4/AIN6_5") (pintype "bidirectional"))
    )
    (net (code "74") (name "unconnected-(U$1B-PB05{slash}I5{slash}AIN7-Pad6)") (class "Default")
      (node (ref "U$1") (pin "6") (pinfunction "PB05/I5/AIN7_6") (pintype "bidirectional"))
    )
    (net (code "75") (name "unconnected-(U$1B-PB23{slash}I7{slash}SERCOM1+5.3-Pad50)") (class "Default")
      (node (ref "U$1") (pin "50") (pinfunction "PB23/I7/SERCOM1+5.3_50") (pintype "bidirectional"))
    )
    (net (code "76") (name "unconnected-(U$1B-PB31{slash}I15{slash}SERCOM5.0-Pad60)") (class "Default")
      (node (ref "U$1") (pin "60") (pinfunction "PB31/I15/SERCOM5.0_60") (pintype "bidirectional"))
    )
    (net (code "77") (name "unconnected-(U2-NC{slash}FB-Pad4)") (class "Default")
      (node (ref "U2") (pin "4") (pinfunction "NC/FB_4") (pintype "passive"))
    )
    (net (code "78") (name "unconnected-(X2-GNDDETECT-Pad9)") (class "Default")
      (node (ref "X2") (pin "9") (pinfunction "GNDDETECT_9") (pintype "bidirectional"))
    )
    (net (code "79") (name "unconnected-(X2-KEY-Pad7)") (class "Default")
      (node (ref "X2") (pin "7") (pinfunction "KEY_7") (pintype "bidirectional"))
    )
    (net (code "80") (name "unconnected-(X2-TDI-Pad8)") (class "Default")
      (node (ref "X2") (pin "8") (pinfunction "TDI_8") (pintype "bidirectional"))
    )
  )
)
